# PERIPHERAL_PORT_IO.net
KiCad netlist of a schematic drawn in Altium Designer
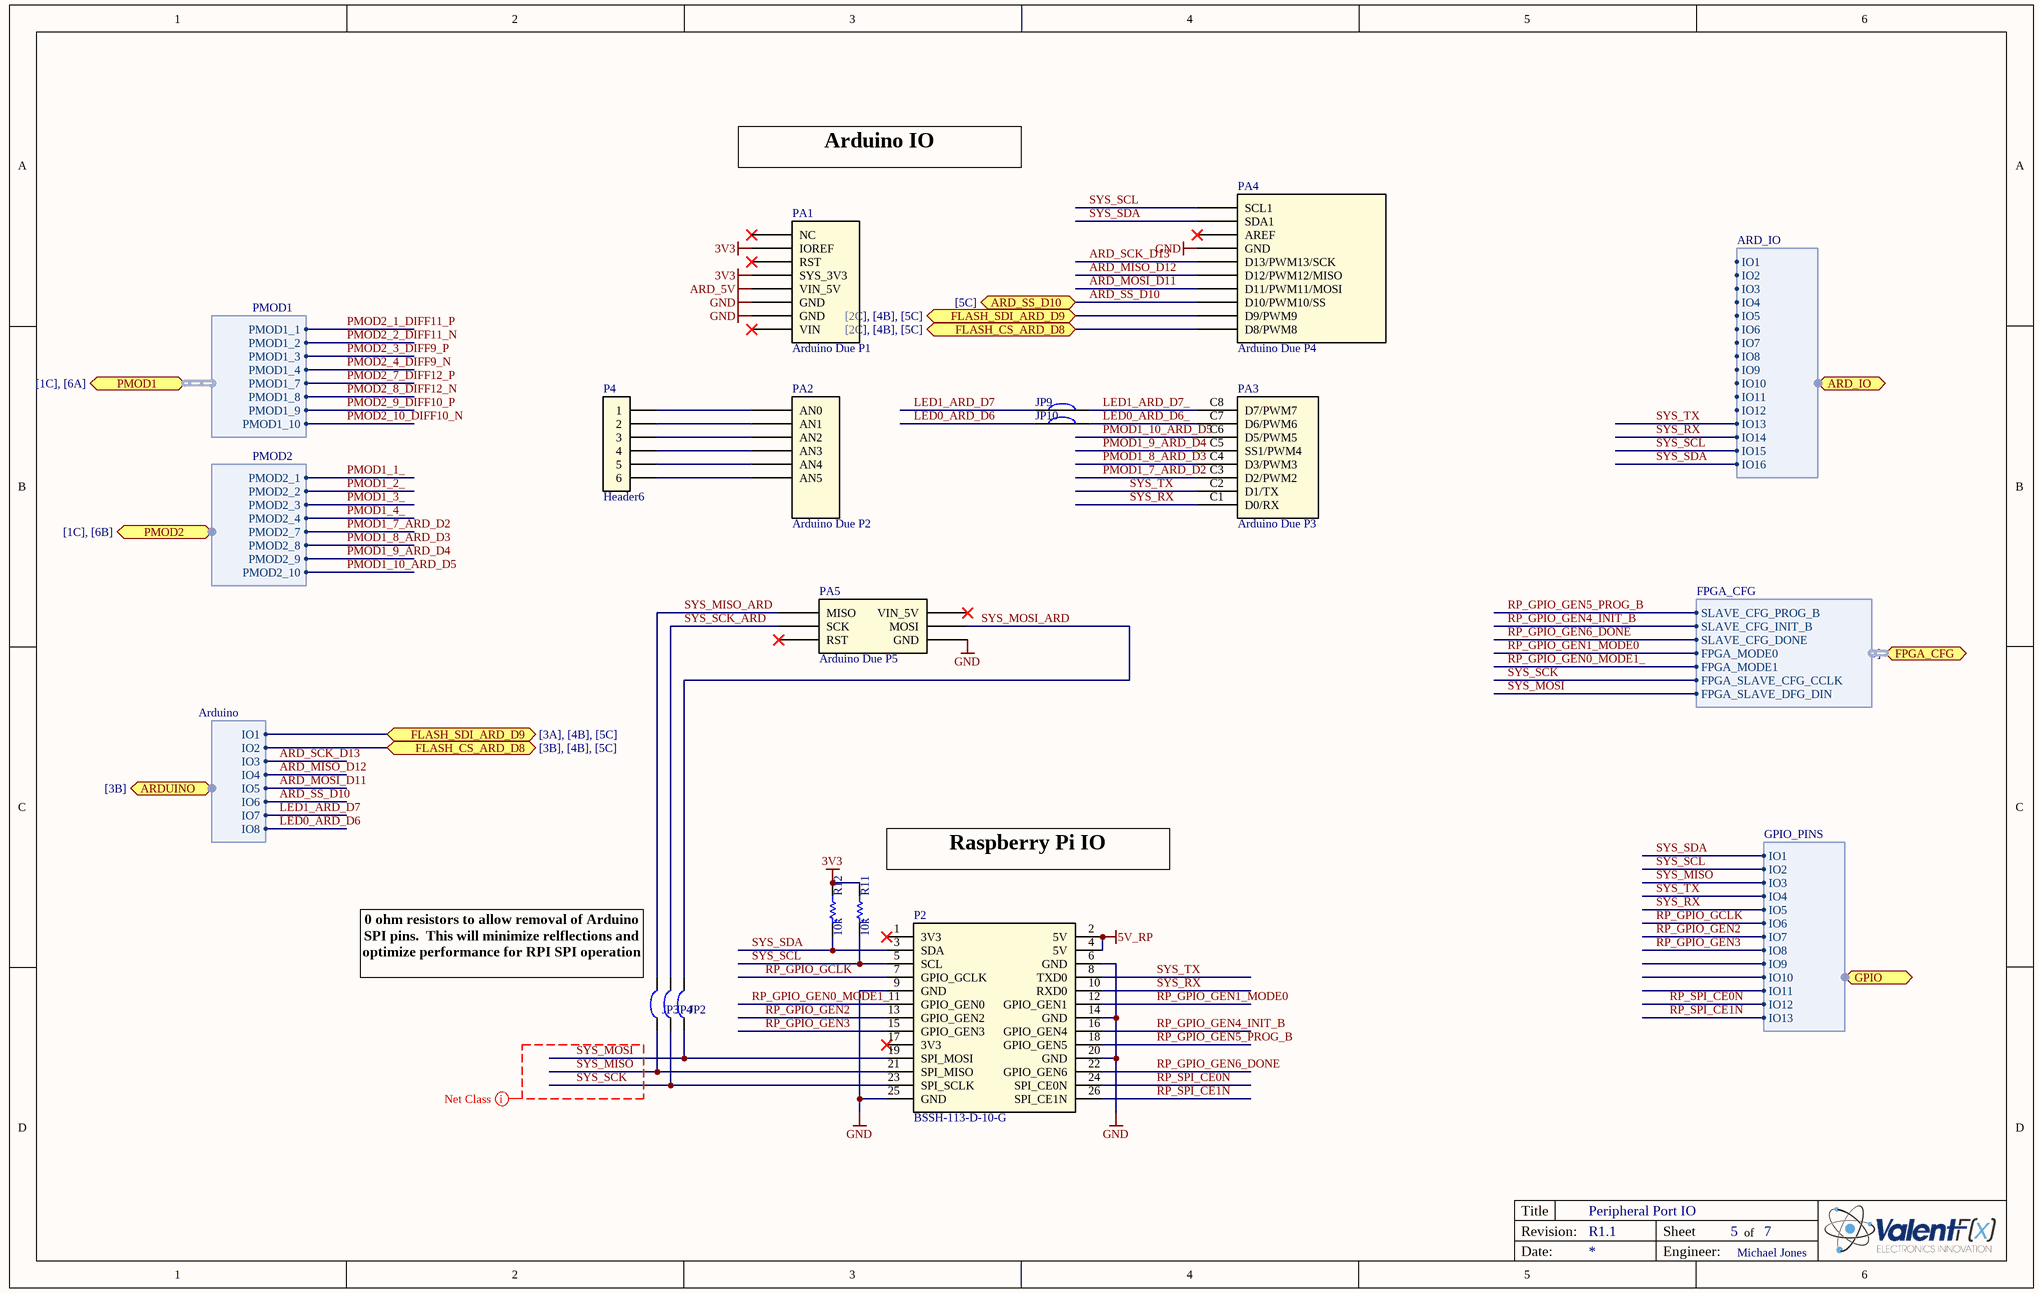
[diagram p0: PERIPHERAL_PORT_IO.SchDoc]

(export (version "E")
  (design (tool "Eeschema 10.0.6"))
  (components
    (comp (ref "JP2")
      (value "Solder Jumper")
      (footprint "SOLDER_JUMPER")
      (description "Solder/Configuration Jumper")
      (fields (field (name "MANUFACTURER") "n/a"))
      (libsource (lib "mConnector") (part "Solder Jumper"))
    )
    (comp (ref "JP3")
      (value "Solder Jumper")
      (footprint "SOLDER_JUMPER")
      (description "Solder/Configuration Jumper")
      (fields (field (name "MANUFACTURER") "n/a"))
      (libsource (lib "mConnector") (part "Solder Jumper"))
    )
    (comp (ref "JP4")
      (value "Solder Jumper")
      (footprint "SOLDER_JUMPER")
      (description "Solder/Configuration Jumper")
      (fields (field (name "MANUFACTURER") "n/a"))
      (libsource (lib "mConnector") (part "Solder Jumper"))
    )
    (comp (ref "JP9")
      (value "Solder Jumper-NC")
      (footprint "SOLDER_JUMPER-NC")
      (description "Solder/Configuration Jumper")
      (fields (field (name "MANUFACTURER") "n/a"))
      (libsource (lib "mConnector") (part "Solder Jumper-NC"))
    )
    (comp (ref "JP10")
      (value "Solder Jumper-NC")
      (footprint "SOLDER_JUMPER-NC")
      (description "Solder/Configuration Jumper")
      (fields (field (name "MANUFACTURER") "n/a"))
      (libsource (lib "mConnector") (part "Solder Jumper-NC"))
    )
    (comp (ref "P2")
      (value "BSSH-113-D-10-G")
      (footprint "Raspberr Pi - 26")
      (description "Raspberry Pi - 26")
      (fields (field (name "MANUFACTURER") "Major League Electroncis"))
      (libsource (lib "mConnector") (part "Raspberry Pi - 26"))
    )
    (comp (ref "P4")
      (value "Header6")
      (footprint "HEADER_6_40_100 THRU SIP")
      (description "Header 6 pin")
      (libsource (lib "mConnector") (part "Header6"))
    )
    (comp (ref "PA1")
      (value "Arduino Due P1")
      (footprint "Arduino Due P1")
      (description "CONN HEADER FEMALE 8POS .1\" GOLD")
      (fields
        (field (name "MANUFACTURER") "Sullins Connector Solutions")
        (field (name "MANUFACTURER PART NUMBER") "PPPC081LFBN-RC")
      )
      (libsource (lib "mConnector") (part "Arduino Due P1"))
    )
    (comp (ref "PA2")
      (value "Arduino Due P2")
      (footprint "Arduino Due P2")
      (description "CONN HEADER FEMALE 6POS .1\" GOLD")
      (fields
        (field (name "MANUFACTURER") "Sullins Connector Solutions")
        (field (name "MANUFACTURER PART NUMBER") "PPPC061LFBN-RC")
      )
      (libsource (lib "mConnector") (part "Arduino Due P2"))
    )
    (comp (ref "PA3")
      (value "Arduino Due P3")
      (footprint "Arduino Due P3")
      (description "CONN HEADER FEMALE 8POS .1\" GOLD")
      (fields
        (field (name "MANUFACTURER") "Sullins Connector Solutions")
        (field (name "MANUFACTURER PART NUMBER") "PPPC081LFBN-RC")
      )
      (libsource (lib "mConnector") (part "Arduino Due P3"))
    )
    (comp (ref "PA4")
      (value "Arduino Due P4")
      (footprint "Arduino Due P4")
      (description "CONN HEADER FMALE 10POS .1\" GOLD")
      (fields
        (field (name "MANUFACTURER") "Sullins Connector Solutions")
        (field (name "MANUFACTURER PART NUMBER") "PPPC101LFBN-RC")
      )
      (libsource (lib "mConnector") (part "Arduino Due P4"))
    )
    (comp (ref "PA5")
      (value "Arduino Due P5")
      (footprint "Arduino Due P5")
      (libsource (lib "mConnector") (part "Arduino Due P5"))
    )
    (comp (ref "R11")
      (value "10k")
      (footprint "mRCL:R0603")
      (description "10k Thick Film Resistors - SMD 1/10watt 10Kohms 1%")
      (fields
        (field (name "MANUFACTURER") "Vishay Dale")
        (field (name "MANUFACTURER PART NUMBER") "CRCW060310K0FKEA")
      )
      (libsource (lib "mResistors") (part "R0603 - CRCW060310K0FKEA"))
    )
    (comp (ref "R12")
      (value "10k")
      (footprint "mRCL:R0603")
      (description "10k Thick Film Resistors - SMD 1/10watt 10Kohms 1%")
      (fields
        (field (name "MANUFACTURER") "Vishay Dale")
        (field (name "MANUFACTURER PART NUMBER") "CRCW060310K0FKEA")
      )
      (libsource (lib "mResistors") (part "R0603 - CRCW060310K0FKEA"))
    )
  )
  (nets
    (net (code "7") (name "/ARD_MISO_D12") (class "Default")
      (node (ref "PA4") (pin "D5") (pinfunction "D12/PWM12/MISO_D5") (pintype "passive"))
    )
    (net (code "8") (name "/ARD_MOSI_D11") (class "Default")
      (node (ref "PA4") (pin "D4") (pinfunction "D11/PWM11/MOSI_D4") (pintype "passive"))
    )
    (net (code "9") (name "/ARD_SCK_D13") (class "Default")
      (node (ref "PA4") (pin "D6") (pinfunction "D13/PWM13/SCK_D6") (pintype "passive"))
    )
    (net (code "10") (name "/ARD_SS_D10") (class "Default")
      (node (ref "PA4") (pin "D3") (pinfunction "D10/PWM10/SS_D3") (pintype "passive"))
    )
    (net (code "11") (name "/FLASH_CS_ARD_D8") (class "Default")
      (node (ref "PA4") (pin "D1") (pinfunction "D8/PWM8_D1") (pintype "passive"))
    )
    (net (code "12") (name "/FLASH_SDI_ARD_D9") (class "Default")
      (node (ref "PA4") (pin "D2") (pinfunction "D9/PWM9_D2") (pintype "passive"))
    )
    (net (code "13") (name "/LED0_ARD_D6") (class "Default")
      (node (ref "JP10") (pin "1") (pinfunction "1_1") (pintype "passive"))
    )
    (net (code "14") (name "/LED0_ARD_D6_") (class "Default")
      (node (ref "JP10") (pin "2") (pinfunction "2_2") (pintype "passive"))
      (node (ref "PA3") (pin "C7") (pinfunction "D6/PWM6_C7") (pintype "passive"))
    )
    (net (code "15") (name "/LED1_ARD_D7") (class "Default")
      (node (ref "JP9") (pin "1") (pinfunction "1_1") (pintype "passive"))
    )
    (net (code "16") (name "/LED1_ARD_D7_") (class "Default")
      (node (ref "JP9") (pin "2") (pinfunction "2_2") (pintype "passive"))
      (node (ref "PA3") (pin "C8") (pinfunction "D7/PWM7_C8") (pintype "passive"))
    )
    (net (code "21") (name "/PMOD1_7_ARD_D2") (class "Default")
      (node (ref "PA3") (pin "C3") (pinfunction "D2/PWM2_C3") (pintype "passive"))
    )
    (net (code "22") (name "/PMOD1_8_ARD_D3") (class "Default")
      (node (ref "PA3") (pin "C4") (pinfunction "D3/PWM3_C4") (pintype "passive"))
    )
    (net (code "23") (name "/PMOD1_9_ARD_D4") (class "Default")
      (node (ref "PA3") (pin "C5") (pinfunction "SS1/PWM4_C5") (pintype "passive"))
    )
    (net (code "24") (name "/PMOD1_10_ARD_D5") (class "Default")
      (node (ref "PA3") (pin "C6") (pinfunction "D5/PWM5_C6") (pintype "passive"))
    )
    (net (code "33") (name "/RP_GPIO_GCLK") (class "Default")
      (node (ref "P2") (pin "7") (pinfunction "GPIO_GCLK_7") (pintype "passive"))
    )
    (net (code "34") (name "/RP_GPIO_GEN0_MODE1_") (class "Default")
      (node (ref "P2") (pin "11") (pinfunction "GPIO_GEN0_11") (pintype "passive"))
    )
    (net (code "35") (name "/RP_GPIO_GEN1_MODE0") (class "Default")
      (node (ref "P2") (pin "12") (pinfunction "GPIO_GEN1_12") (pintype "passive"))
    )
    (net (code "36") (name "/RP_GPIO_GEN2") (class "Default")
      (node (ref "P2") (pin "13") (pinfunction "GPIO_GEN2_13") (pintype "passive"))
    )
    (net (code "37") (name "/RP_GPIO_GEN3") (class "Default")
      (node (ref "P2") (pin "15") (pinfunction "GPIO_GEN3_15") (pintype "passive"))
    )
    (net (code "38") (name "/RP_GPIO_GEN4_INIT_B") (class "Default")
      (node (ref "P2") (pin "16") (pinfunction "GPIO_GEN4_16") (pintype "passive"))
    )
    (net (code "39") (name "/RP_GPIO_GEN5_PROG_B") (class "Default")
      (node (ref "P2") (pin "18") (pinfunction "GPIO_GEN5_18") (pintype "passive"))
    )
    (net (code "40") (name "/RP_GPIO_GEN6_DONE") (class "Default")
      (node (ref "P2") (pin "22") (pinfunction "GPIO_GEN6_22") (pintype "passive"))
    )
    (net (code "41") (name "/RP_SPI_CE0N") (class "Default")
      (node (ref "P2") (pin "24") (pinfunction "SPI_CE0N_24") (pintype "passive"))
    )
    (net (code "42") (name "/RP_SPI_CE1N") (class "Default")
      (node (ref "P2") (pin "26") (pinfunction "SPI_CE1N_26") (pintype "passive"))
    )
    (net (code "43") (name "/SYS_MISO") (class "Default")
      (node (ref "JP3") (pin "1") (pinfunction "1_1") (pintype "passive"))
      (node (ref "P2") (pin "21") (pinfunction "SPI_MISO_21") (pintype "passive"))
    )
    (net (code "44") (name "/SYS_MISO_ARD") (class "Default")
      (node (ref "JP3") (pin "2") (pinfunction "2_2") (pintype "passive"))
      (node (ref "PA5") (pin "E1") (pinfunction "MISO_E1") (pintype "passive"))
    )
    (net (code "45") (name "/SYS_MOSI") (class "Default")
      (node (ref "JP2") (pin "1") (pinfunction "1_1") (pintype "passive"))
      (node (ref "P2") (pin "19") (pinfunction "SPI_MOSI_19") (pintype "passive"))
    )
    (net (code "46") (name "/SYS_MOSI_ARD") (class "Default")
      (node (ref "JP2") (pin "2") (pinfunction "2_2") (pintype "passive"))
      (node (ref "PA5") (pin "E4") (pinfunction "MOSI_E4") (pintype "passive"))
    )
    (net (code "47") (name "/SYS_RX") (class "Default")
      (node (ref "P2") (pin "10") (pinfunction "RXD0_10") (pintype "passive"))
      (node (ref "PA3") (pin "C1") (pinfunction "D0/RX_C1") (pintype "passive"))
    )
    (net (code "48") (name "/SYS_SCK") (class "Default")
      (node (ref "JP4") (pin "1") (pinfunction "1_1") (pintype "passive"))
      (node (ref "P2") (pin "23") (pinfunction "SPI_SCLK_23") (pintype "passive"))
    )
    (net (code "49") (name "/SYS_SCK_ARD") (class "Default")
      (node (ref "JP4") (pin "2") (pinfunction "2_2") (pintype "passive"))
      (node (ref "PA5") (pin "E3") (pinfunction "SCK_E3") (pintype "passive"))
    )
    (net (code "50") (name "/SYS_SCL") (class "Default")
      (node (ref "P2") (pin "5") (pinfunction "SCL_5") (pintype "passive"))
      (node (ref "PA4") (pin "D10") (pinfunction "SCL1_D10") (pintype "passive"))
      (node (ref "R11") (pin "1") (pinfunction "1_1") (pintype "passive"))
    )
    (net (code "51") (name "/SYS_SDA") (class "Default")
      (node (ref "P2") (pin "3") (pinfunction "SDA_3") (pintype "passive"))
      (node (ref "PA4") (pin "D9") (pinfunction "SDA1_D9") (pintype "passive"))
      (node (ref "R12") (pin "1") (pinfunction "1_1") (pintype "passive"))
    )
    (net (code "52") (name "/SYS_TX") (class "Default")
      (node (ref "P2") (pin "8") (pinfunction "TXD0_8") (pintype "passive"))
      (node (ref "PA3") (pin "C2") (pinfunction "D1/TX_C2") (pintype "passive"))
    )
    (net (code "59") (name "3V3") (class "Default")
      (node (ref "PA1") (pin "A2") (pinfunction "IOREF_A2") (pintype "passive"))
      (node (ref "PA1") (pin "A4") (pinfunction "SYS_3V3_A4") (pintype "passive"))
      (node (ref "R11") (pin "2") (pinfunction "2_2") (pintype "passive"))
      (node (ref "R12") (pin "2") (pinfunction "2_2") (pintype "passive"))
    )
    (net (code "60") (name "5V_RP") (class "Default")
      (node (ref "P2") (pin "2") (pinfunction "5V_2") (pintype "passive"))
      (node (ref "P2") (pin "4") (pinfunction "5V_4") (pintype "passive"))
    )
    (net (code "61") (name "ARD_5V") (class "Default")
      (node (ref "PA1") (pin "A5") (pinfunction "VIN_5V_A5") (pintype "passive"))
    )
    (net (code "62") (name "GND") (class "Default")
      (node (ref "P2") (pin "14") (pinfunction "GND_14") (pintype "passive"))
      (node (ref "P2") (pin "20") (pinfunction "GND_20") (pintype "passive"))
      (node (ref "P2") (pin "25") (pinfunction "GND_25") (pintype "passive"))
      (node (ref "P2") (pin "6") (pinfunction "GND_6") (pintype "passive"))
      (node (ref "P2") (pin "9") (pinfunction "GND_9") (pintype "passive"))
      (node (ref "PA1") (pin "A6") (pinfunction "GND_A6") (pintype "passive"))
      (node (ref "PA1") (pin "A7") (pinfunction "GND_A7") (pintype "passive"))
      (node (ref "PA4") (pin "D7") (pinfunction "GND_D7") (pintype "passive"))
      (node (ref "PA5") (pin "E6") (pinfunction "GND_E6") (pintype "passive"))
    )
    (net (code "63") (name "Net-(PA2-AN0)") (class "Default")
      (node (ref "P4") (pin "1") (pinfunction "1_1") (pintype "passive"))
      (node (ref "PA2") (pin "B1") (pinfunction "AN0_B1") (pintype "passive"))
    )
    (net (code "64") (name "Net-(PA2-AN1)") (class "Default")
      (node (ref "P4") (pin "2") (pinfunction "2_2") (pintype "passive"))
      (node (ref "PA2") (pin "B2") (pinfunction "AN1_B2") (pintype "passive"))
    )
    (net (code "65") (name "Net-(PA2-AN2)") (class "Default")
      (node (ref "P4") (pin "3") (pinfunction "3_3") (pintype "passive"))
      (node (ref "PA2") (pin "B3") (pinfunction "AN2_B3") (pintype "passive"))
    )
    (net (code "66") (name "Net-(PA2-AN3)") (class "Default")
      (node (ref "P4") (pin "4") (pinfunction "4_4") (pintype "passive"))
      (node (ref "PA2") (pin "B4") (pinfunction "AN3_B4") (pintype "passive"))
    )
    (net (code "67") (name "Net-(PA2-AN4)") (class "Default")
      (node (ref "P4") (pin "5") (pinfunction "5_5") (pintype "passive"))
      (node (ref "PA2") (pin "B5") (pinfunction "AN4_B5") (pintype "passive"))
    )
    (net (code "68") (name "Net-(PA2-AN5)") (class "Default")
      (node (ref "P4") (pin "6") (pinfunction "6_6") (pintype "passive"))
      (node (ref "PA2") (pin "B6") (pinfunction "AN5_B6") (pintype "passive"))
    )
    (net (code "69") (name "unconnected-(P2-3V3-Pad1)") (class "Default")
      (node (ref "P2") (pin "1") (pinfunction "3V3_1") (pintype "passive+no_connect"))
    )
    (net (code "70") (name "unconnected-(P2-3V3-Pad17)") (class "Default")
      (node (ref "P2") (pin "17") (pinfunction "3V3_17") (pintype "passive+no_connect"))
    )
    (net (code "71") (name "unconnected-(PA1-NC-PadA1)") (class "Default")
      (node (ref "PA1") (pin "A1") (pinfunction "NC_A1") (pintype "passive+no_connect"))
    )
    (net (code "72") (name "unconnected-(PA1-RST-PadA3)") (class "Default")
      (node (ref "PA1") (pin "A3") (pinfunction "RST_A3") (pintype "passive+no_connect"))
    )
    (net (code "73") (name "unconnected-(PA1-VIN-PadA8)") (class "Default")
      (node (ref "PA1") (pin "A8") (pinfunction "VIN_A8") (pintype "passive+no_connect"))
    )
    (net (code "74") (name "unconnected-(PA4-AREF-PadD8)") (class "Default")
      (node (ref "PA4") (pin "D8") (pinfunction "AREF_D8") (pintype "passive+no_connect"))
    )
    (net (code "75") (name "unconnected-(PA5-RST-PadE5)") (class "Default")
      (node (ref "PA5") (pin "E5") (pinfunction "RST_E5") (pintype "passive+no_connect"))
    )
    (net (code "76") (name "unconnected-(PA5-VIN_5V-PadE2)") (class "Default")
      (node (ref "PA5") (pin "E2") (pinfunction "VIN_5V_E2") (pintype "passive+no_connect"))
    )
  )
)
